# Sample_End_Effector.net
KiCad netlist of a schematic drawn in EAGLE
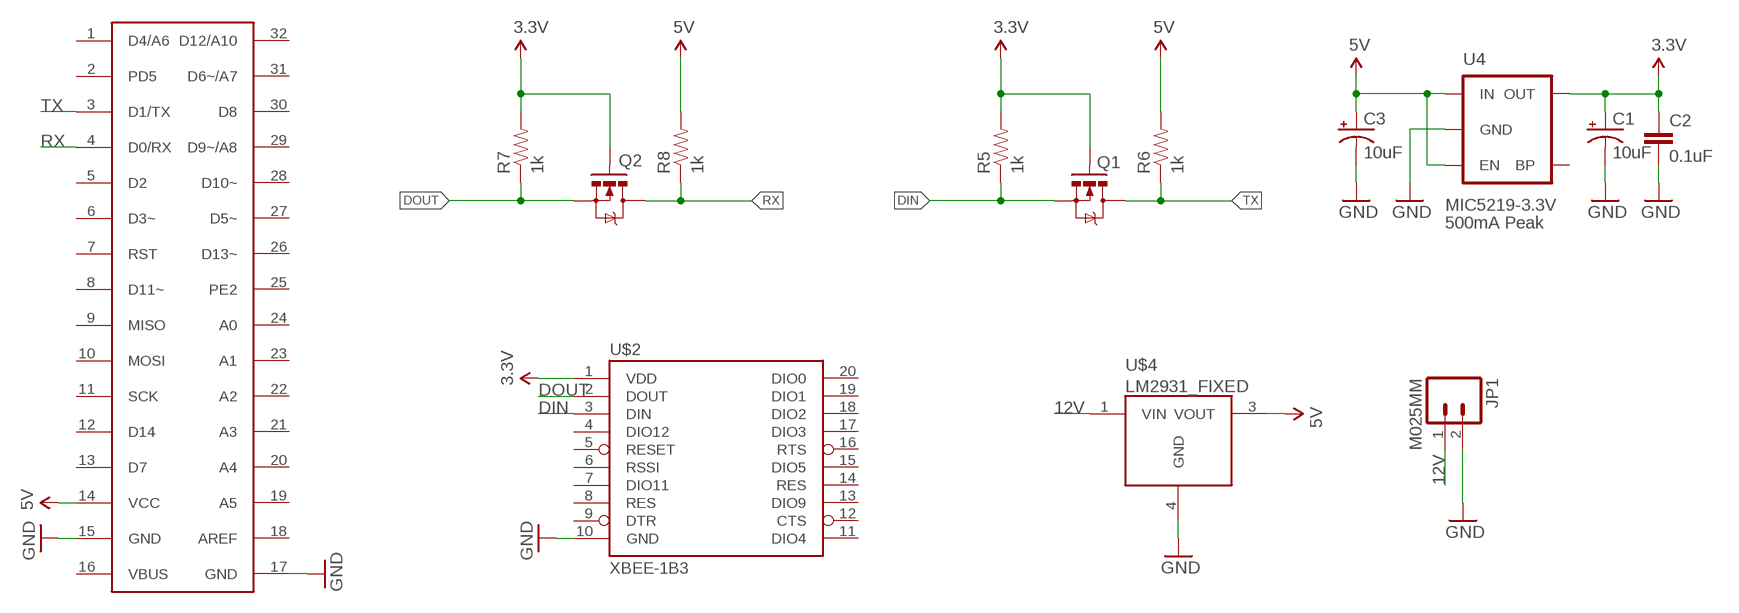
[diagram p0: schematic, sheet 1]

(export (version "E")
  (design (tool "Eeschema 10.0.6"))
  (components
    (comp (ref "C1")
      (value "10uF")
      (footprint "eagle-import:EIA3216")
      (libsource (lib "eagle-import") (part "CAP_POL1206"))
    )
    (comp (ref "C2")
      (value "0.1uF")
      (footprint "eagle-import:0603-CAP")
      (libsource (lib "eagle-import") (part "0.1UF-25V(+80/-20%)(0603)"))
    )
    (comp (ref "C3")
      (value "10uF")
      (footprint "eagle-import:EIA3216")
      (libsource (lib "eagle-import") (part "CAP_POL1206"))
    )
    (comp (ref "JP1")
      (value "M025MM")
      (footprint "eagle-import:SCREWTERMINAL-5MM-2")
      (libsource (lib "eagle-import") (part "M025MM"))
    )
    (comp (ref "Q1")
      (value "MOSFET-NCHANNELSMD")
      (footprint "eagle-import:SOT23-3")
      (libsource (lib "eagle-import") (part "MOSFET-NCHANNELSMD"))
    )
    (comp (ref "Q2")
      (value "MOSFET-NCHANNELSMD")
      (footprint "eagle-import:SOT23-3")
      (libsource (lib "eagle-import") (part "MOSFET-NCHANNELSMD"))
    )
    (comp (ref "R5")
      (value "1k")
      (footprint "eagle-import:0603-RES")
      (libsource (lib "eagle-import") (part "1KOHM1/10W1%(0603)"))
    )
    (comp (ref "R6")
      (value "1k")
      (footprint "eagle-import:0603-RES")
      (libsource (lib "eagle-import") (part "1KOHM1/10W1%(0603)"))
    )
    (comp (ref "R7")
      (value "1k")
      (footprint "eagle-import:0603-RES")
      (libsource (lib "eagle-import") (part "1KOHM1/10W1%(0603)"))
    )
    (comp (ref "R8")
      (value "1k")
      (footprint "eagle-import:0603-RES")
      (libsource (lib "eagle-import") (part "1KOHM1/10W1%(0603)"))
    )
    (comp (ref "U$1")
      (value "32U4")
      (footprint "eagle-import:DIP")
      (libsource (lib "eagle-import") (part "32U4"))
    )
    (comp (ref "U$2")
      (value "XBEE-1B3")
      (footprint "eagle-import:XBEE-SMD")
      (libsource (lib "eagle-import") (part "XBEE-1B3"))
    )
    (comp (ref "U$4")
      (value "LM2931_FIXED")
      (footprint "eagle-import:DPAK")
      (libsource (lib "eagle-import") (part "LM2931_FIXED"))
    )
    (comp (ref "U4")
      (value "V_REG_LDOSMD")
      (footprint "eagle-import:SOT23-5")
      (libsource (lib "eagle-import") (part "V_REG_LDOSMD"))
    )
  )
  (nets
    (net (code "1") (name "/12V") (class "Default")
      (node (ref "JP1") (pin "1") (pinfunction "1_1") (pintype "passive"))
      (node (ref "U$4") (pin "1") (pinfunction "VIN_1") (pintype "bidirectional"))
    )
    (net (code "2") (name "3.3V") (class "Default")
      (node (ref "C1") (pin "A") (pinfunction "+_A") (pintype "passive"))
      (node (ref "C2") (pin "1") (pinfunction "1_1") (pintype "passive"))
      (node (ref "Q1") (pin "1") (pinfunction "G_1") (pintype "passive"))
      (node (ref "Q2") (pin "1") (pinfunction "G_1") (pintype "passive"))
      (node (ref "R5") (pin "2") (pinfunction "2_2") (pintype "passive"))
      (node (ref "R7") (pin "2") (pinfunction "2_2") (pintype "passive"))
      (node (ref "U$2") (pin "1") (pinfunction "VDD_1") (pintype "power_in"))
      (node (ref "U4") (pin "5") (pinfunction "OUT_5") (pintype "passive"))
    )
    (net (code "3") (name "5V") (class "Default")
      (node (ref "C3") (pin "A") (pinfunction "+_A") (pintype "passive"))
      (node (ref "R6") (pin "2") (pinfunction "2_2") (pintype "passive"))
      (node (ref "R8") (pin "2") (pinfunction "2_2") (pintype "passive"))
      (node (ref "U$1") (pin "14") (pinfunction "VCC_14") (pintype "bidirectional"))
      (node (ref "U$4") (pin "3") (pinfunction "VOUT_3") (pintype "bidirectional"))
      (node (ref "U4") (pin "1") (pinfunction "IN_1") (pintype "input"))
      (node (ref "U4") (pin "3") (pinfunction "EN_3") (pintype "input"))
    )
    (net (code "4") (name "DIN") (class "Default")
      (node (ref "Q1") (pin "2") (pinfunction "S_2") (pintype "passive"))
      (node (ref "R5") (pin "1") (pinfunction "1_1") (pintype "passive"))
      (node (ref "U$2") (pin "3") (pinfunction "DIN_3") (pintype "input"))
    )
    (net (code "5") (name "DOUT") (class "Default")
      (node (ref "Q2") (pin "2") (pinfunction "S_2") (pintype "passive"))
      (node (ref "R7") (pin "1") (pinfunction "1_1") (pintype "passive"))
      (node (ref "U$2") (pin "2") (pinfunction "DOUT_2") (pintype "output"))
    )
    (net (code "6") (name "GND") (class "Default")
      (node (ref "C1") (pin "C") (pinfunction "-_C") (pintype "passive"))
      (node (ref "C2") (pin "2") (pinfunction "2_2") (pintype "passive"))
      (node (ref "C3") (pin "C") (pinfunction "-_C") (pintype "passive"))
      (node (ref "JP1") (pin "2") (pinfunction "2_2") (pintype "passive"))
      (node (ref "U$1") (pin "15") (pinfunction "GND_15") (pintype "bidirectional"))
      (node (ref "U$1") (pin "17") (pinfunction "GND_17") (pintype "bidirectional"))
      (node (ref "U$2") (pin "10") (pinfunction "GND_10") (pintype "power_in"))
      (node (ref "U$4") (pin "4") (pinfunction "GND_4") (pintype "bidirectional"))
      (node (ref "U4") (pin "2") (pinfunction "GND_2") (pintype "input"))
    )
    (net (code "7") (name "RX") (class "Default")
      (node (ref "Q2") (pin "3") (pinfunction "D_3") (pintype "passive"))
      (node (ref "R8") (pin "1") (pinfunction "1_1") (pintype "passive"))
      (node (ref "U$1") (pin "4") (pinfunction "D0/RX_4") (pintype "bidirectional"))
    )
    (net (code "8") (name "TX") (class "Default")
      (node (ref "Q1") (pin "3") (pinfunction "D_3") (pintype "passive"))
      (node (ref "R6") (pin "1") (pinfunction "1_1") (pintype "passive"))
      (node (ref "U$1") (pin "3") (pinfunction "D1/TX_3") (pintype "bidirectional"))
    )
    (net (code "9") (name "unconnected-(U$1-A0-Pad24)") (class "Default")
      (node (ref "U$1") (pin "24") (pinfunction "A0_24") (pintype "bidirectional"))
    )
    (net (code "10") (name "unconnected-(U$1-A1-Pad23)") (class "Default")
      (node (ref "U$1") (pin "23") (pinfunction "A1_23") (pintype "bidirectional"))
    )
    (net (code "11") (name "unconnected-(U$1-A2-Pad22)") (class "Default")
      (node (ref "U$1") (pin "22") (pinfunction "A2_22") (pintype "bidirectional"))
    )
    (net (code "12") (name "unconnected-(U$1-A3-Pad21)") (class "Default")
      (node (ref "U$1") (pin "21") (pinfunction "A3_21") (pintype "bidirectional"))
    )
    (net (code "13") (name "unconnected-(U$1-A4-Pad20)") (class "Default")
      (node (ref "U$1") (pin "20") (pinfunction "A4_20") (pintype "bidirectional"))
    )
    (net (code "14") (name "unconnected-(U$1-A5-Pad19)") (class "Default")
      (node (ref "U$1") (pin "19") (pinfunction "A5_19") (pintype "bidirectional"))
    )
    (net (code "15") (name "unconnected-(U$1-AREF-Pad18)") (class "Default")
      (node (ref "U$1") (pin "18") (pinfunction "AREF_18") (pintype "bidirectional"))
    )
    (net (code "16") (name "unconnected-(U$1-D2-Pad5)") (class "Default")
      (node (ref "U$1") (pin "5") (pinfunction "D2_5") (pintype "bidirectional"))
    )
    (net (code "17") (name "unconnected-(U$1-D3~{}-Pad6)") (class "Default")
      (node (ref "U$1") (pin "6") (pinfunction "D3~{}_6") (pintype "bidirectional"))
    )
    (net (code "18") (name "unconnected-(U$1-D4{slash}A6-Pad1)") (class "Default")
      (node (ref "U$1") (pin "1") (pinfunction "D4/A6_1") (pintype "bidirectional"))
    )
    (net (code "19") (name "unconnected-(U$1-D5~{}-Pad27)") (class "Default")
      (node (ref "U$1") (pin "27") (pinfunction "D5~{}_27") (pintype "bidirectional"))
    )
    (net (code "20") (name "unconnected-(U$1-D6~{{slash}A7}-Pad31)") (class "Default")
      (node (ref "U$1") (pin "31") (pinfunction "D6~{/A7}_31") (pintype "bidirectional"))
    )
    (net (code "21") (name "unconnected-(U$1-D7-Pad13)") (class "Default")
      (node (ref "U$1") (pin "13") (pinfunction "D7_13") (pintype "bidirectional"))
    )
    (net (code "22") (name "unconnected-(U$1-D8-Pad30)") (class "Default")
      (node (ref "U$1") (pin "30") (pinfunction "D8_30") (pintype "bidirectional"))
    )
    (net (code "23") (name "unconnected-(U$1-D9~{{slash}A8}-Pad29)") (class "Default")
      (node (ref "U$1") (pin "29") (pinfunction "D9~{/A8}_29") (pintype "bidirectional"))
    )
    (net (code "24") (name "unconnected-(U$1-D10~{}-Pad28)") (class "Default")
      (node (ref "U$1") (pin "28") (pinfunction "D10~{}_28") (pintype "bidirectional"))
    )
    (net (code "25") (name "unconnected-(U$1-D11~{}-Pad8)") (class "Default")
      (node (ref "U$1") (pin "8") (pinfunction "D11~{}_8") (pintype "bidirectional"))
    )
    (net (code "26") (name "unconnected-(U$1-D12{slash}A10-Pad32)") (class "Default")
      (node (ref "U$1") (pin "32") (pinfunction "D12/A10_32") (pintype "bidirectional"))
    )
    (net (code "27") (name "unconnected-(U$1-D13~{}-Pad26)") (class "Default")
      (node (ref "U$1") (pin "26") (pinfunction "D13~{}_26") (pintype "bidirectional"))
    )
    (net (code "28") (name "unconnected-(U$1-D14-Pad12)") (class "Default")
      (node (ref "U$1") (pin "12") (pinfunction "D14_12") (pintype "bidirectional"))
    )
    (net (code "29") (name "unconnected-(U$1-MISO-Pad9)") (class "Default")
      (node (ref "U$1") (pin "9") (pinfunction "MISO_9") (pintype "bidirectional"))
    )
    (net (code "30") (name "unconnected-(U$1-MOSI-Pad10)") (class "Default")
      (node (ref "U$1") (pin "10") (pinfunction "MOSI_10") (pintype "bidirectional"))
    )
    (net (code "31") (name "unconnected-(U$1-PD5-Pad2)") (class "Default")
      (node (ref "U$1") (pin "2") (pinfunction "PD5_2") (pintype "bidirectional"))
    )
    (net (code "32") (name "unconnected-(U$1-PE2-Pad25)") (class "Default")
      (node (ref "U$1") (pin "25") (pinfunction "PE2_25") (pintype "bidirectional"))
    )
    (net (code "33") (name "unconnected-(U$1-RST-Pad7)") (class "Default")
      (node (ref "U$1") (pin "7") (pinfunction "RST_7") (pintype "bidirectional"))
    )
    (net (code "34") (name "unconnected-(U$1-SCK-Pad11)") (class "Default")
      (node (ref "U$1") (pin "11") (pinfunction "SCK_11") (pintype "bidirectional"))
    )
    (net (code "35") (name "unconnected-(U$1-VBUS-Pad16)") (class "Default")
      (node (ref "U$1") (pin "16") (pinfunction "VBUS_16") (pintype "bidirectional"))
    )
    (net (code "36") (name "unconnected-(U$2-CTS-Pad12)") (class "Default")
      (node (ref "U$2") (pin "12") (pinfunction "CTS_12") (pintype "output"))
    )
    (net (code "37") (name "unconnected-(U$2-DIO0-Pad20)") (class "Default")
      (node (ref "U$2") (pin "20") (pinfunction "DIO0_20") (pintype "bidirectional"))
    )
    (net (code "38") (name "unconnected-(U$2-DIO1-Pad19)") (class "Default")
      (node (ref "U$2") (pin "19") (pinfunction "DIO1_19") (pintype "bidirectional"))
    )
    (net (code "39") (name "unconnected-(U$2-DIO2-Pad18)") (class "Default")
      (node (ref "U$2") (pin "18") (pinfunction "DIO2_18") (pintype "bidirectional"))
    )
    (net (code "40") (name "unconnected-(U$2-DIO3-Pad17)") (class "Default")
      (node (ref "U$2") (pin "17") (pinfunction "DIO3_17") (pintype "bidirectional"))
    )
    (net (code "41") (name "unconnected-(U$2-DIO4-Pad11)") (class "Default")
      (node (ref "U$2") (pin "11") (pinfunction "DIO4_11") (pintype "bidirectional"))
    )
    (net (code "42") (name "unconnected-(U$2-DIO5-Pad15)") (class "Default")
      (node (ref "U$2") (pin "15") (pinfunction "DIO5_15") (pintype "bidirectional"))
    )
    (net (code "43") (name "unconnected-(U$2-DIO9-Pad13)") (class "Default")
      (node (ref "U$2") (pin "13") (pinfunction "DIO9_13") (pintype "bidirectional"))
    )
    (net (code "44") (name "unconnected-(U$2-DIO11-Pad7)") (class "Default")
      (node (ref "U$2") (pin "7") (pinfunction "DIO11_7") (pintype "bidirectional"))
    )
    (net (code "45") (name "unconnected-(U$2-DIO12-Pad4)") (class "Default")
      (node (ref "U$2") (pin "4") (pinfunction "DIO12_4") (pintype "bidirectional"))
    )
    (net (code "46") (name "unconnected-(U$2-DTR-Pad9)") (class "Default")
      (node (ref "U$2") (pin "9") (pinfunction "DTR_9") (pintype "bidirectional"))
    )
    (net (code "47") (name "unconnected-(U$2-RES-Pad8)") (class "Default")
      (node (ref "U$2") (pin "8") (pinfunction "RES_8") (pintype "bidirectional"))
    )
    (net (code "48") (name "unconnected-(U$2-RES-Pad14)") (class "Default")
      (node (ref "U$2") (pin "14") (pinfunction "RES_14") (pintype "bidirectional"))
    )
    (net (code "49") (name "unconnected-(U$2-RESET-Pad5)") (class "Default")
      (node (ref "U$2") (pin "5") (pinfunction "RESET_5") (pintype "input"))
    )
    (net (code "50") (name "unconnected-(U$2-RSSI-Pad6)") (class "Default")
      (node (ref "U$2") (pin "6") (pinfunction "RSSI_6") (pintype "bidirectional"))
    )
    (net (code "51") (name "unconnected-(U$2-RTS-Pad16)") (class "Default")
      (node (ref "U$2") (pin "16") (pinfunction "RTS_16") (pintype "input"))
    )
    (net (code "52") (name "unconnected-(U4-BP-Pad4)") (class "Default")
      (node (ref "U4") (pin "4") (pinfunction "BP_4") (pintype "input"))
    )
  )
)
